# 234trw_2020-09-26_01-09-06.net
KiCad netlist of a schematic drawn in EasyEDA
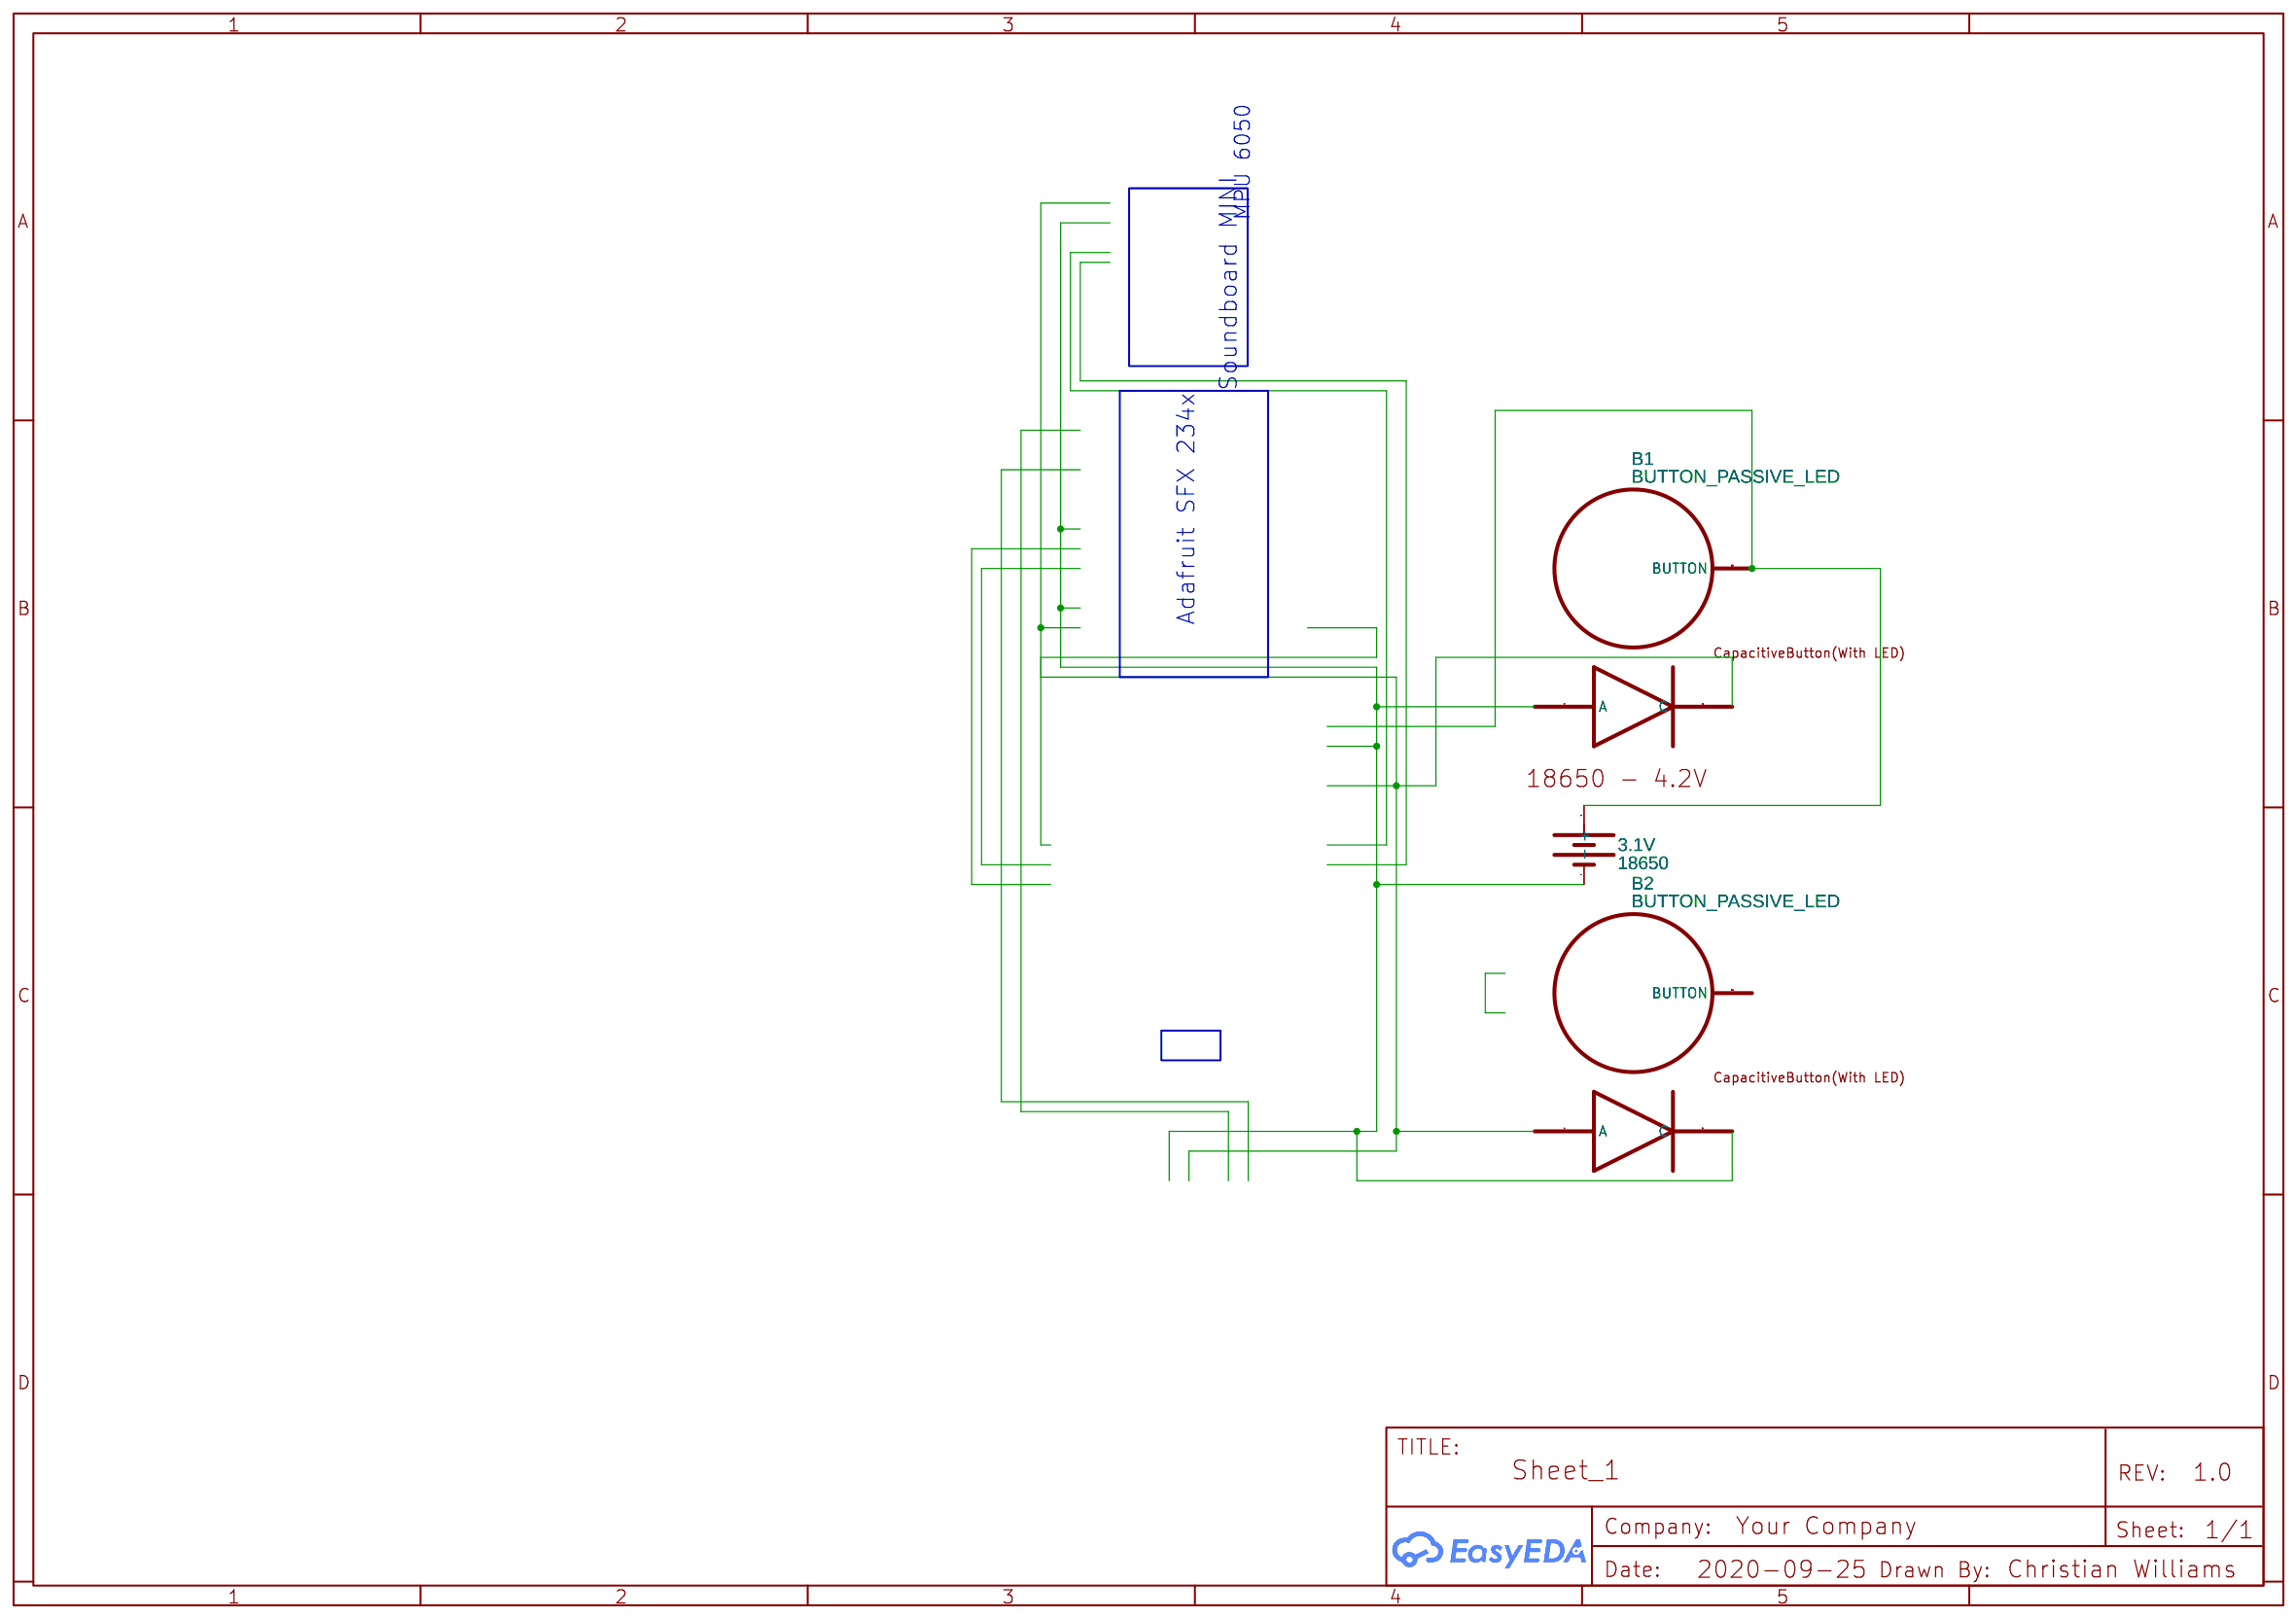
[diagram p0: schematic sheet]

(export (version "E")
  (design (tool "Eeschema 10.0.6"))
  (components
    (comp (ref "3.1V") (value "18650") (libsource (lib "") (part "18650")))
    (comp (ref "B1") (value "BUTTON_PASSIVE_LED") (libsource (lib "") (part "BUTTON_PASSIVE_LED")))
    (comp (ref "B2") (value "BUTTON_PASSIVE_LED") (libsource (lib "") (part "BUTTON_PASSIVE_LED")))
  )
  (nets
    (net (code "1") (name "Net-(3.1V-Pad+)") (class "Default")
      (node (ref "3.1V") (pin "+") (pinfunction "+_+") (pintype "passive"))
      (node (ref "B1") (pin "BUTTON") (pinfunction "BUTTON_BUTTON") (pintype "unspecified"))
    )
    (net (code "2") (name "Net-(3.1V-Pad-)") (class "Default")
      (node (ref "3.1V") (pin "-") (pinfunction "-_-") (pintype "passive"))
      (node (ref "B1") (pin "A") (pinfunction "A_A") (pintype "unspecified"))
      (node (ref "B2") (pin "C") (pinfunction "C_C") (pintype "unspecified"))
    )
    (net (code "3") (name "Net-(B1-PadC)") (class "Default")
      (node (ref "B1") (pin "C") (pinfunction "C_C") (pintype "unspecified"))
      (node (ref "B2") (pin "A") (pinfunction "A_A") (pintype "unspecified"))
    )
    (net (code "4") (name "unconnected-(B2-PadBUTTON)") (class "Default")
      (node (ref "B2") (pin "BUTTON") (pinfunction "BUTTON_BUTTON") (pintype "unspecified"))
    )
  )
)
